# MEMS_RF.net
KiCad netlist of a schematic drawn in Altium Designer
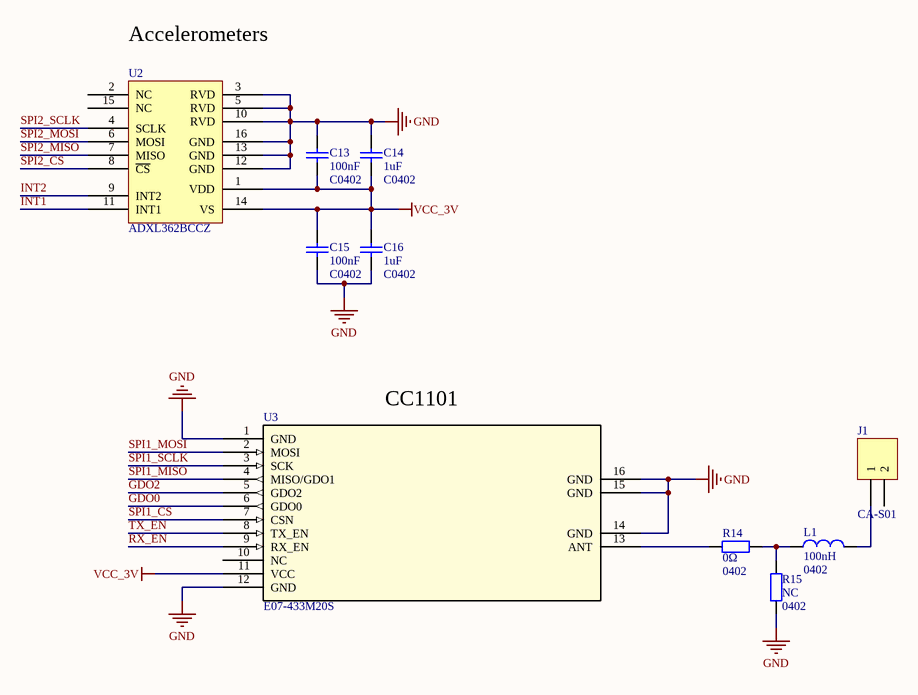
[diagram p0: MEMS&RF.SchDoc]

(export (version "E")
  (design (tool "Eeschema 10.0.6"))
  (components
    (comp (ref "C13")
      (value "100nF")
      (footprint "0402")
      (description "Capacitor (0402,X7R,100nF,DC 50V,±10%) Murata")
      (fields (field (name "PACKAGEREFERENCE") "C0402") (field (name "PUBLISHER") "Altium Limited"))
      (libsource (lib "RFID_CC1101_433MHz") (part "GRM155R71H104KE14"))
    )
    (comp (ref "C14")
      (value "1uF")
      (footprint "0402")
      (description "Capacitor (0402,X5R,1uF,DC 25V,±10%) Murata")
      (fields (field (name "PACKAGEREFERENCE") "C0402") (field (name "PUBLISHER") "Altium Limited"))
      (libsource (lib "RFID_CC1101_433MHz") (part "GRM155R61E105KE11"))
    )
    (comp (ref "C15")
      (value "100nF")
      (footprint "0402")
      (description "Capacitor (0402,X7R,100nF,DC 50V,±10%) Murata")
      (fields (field (name "PACKAGEREFERENCE") "C0402") (field (name "PUBLISHER") "Altium Limited"))
      (libsource (lib "RFID_CC1101_433MHz") (part "GRM155R71H104KE14"))
    )
    (comp (ref "C16")
      (value "1uF")
      (footprint "0402")
      (description "Capacitor (0402,X5R,1uF,DC 25V,±10%) Murata")
      (fields (field (name "PACKAGEREFERENCE") "C0402") (field (name "PUBLISHER") "Altium Limited"))
      (libsource (lib "RFID_CC1101_433MHz") (part "GRM155R61E105KE11"))
    )
    (comp (ref "J1")
      (value "CA-S01")
      (footprint "CA-S01")
      (description "CrossAir Antenna，广州寒武纪电子科技有限公司")
      (fields (field (name "PUBLISHER") "Altium Limited"))
      (libsource (lib "RFID_CC1101_433MHz") (part "CA-S01"))
    )
    (comp (ref "L1")
      (value "100nH")
      (footprint "0402")
      (description "Inductor, 100n, 0402, ±5%, wire-wound type Murata")
      (fields (field (name "PACKAGEREFERENCE") "0402") (field (name "PUBLISHER") "Altium Limited"))
      (libsource (lib "RFID_CC1101_433MHz") (part "LQW15ANR10J00"))
    )
    (comp (ref "R14")
      (value "0Ω")
      (footprint "RESC1005X04N")
      (description "Resistor 0402(1005) 0Ω")
      (fields (field (name "PACKAGEREFERENCE") "0402"))
      (libsource (lib "RFID_CC1101_433MHz") (part "RC0402JR"))
    )
    (comp (ref "R15")
      (value "NC")
      (footprint "RESC1005X04N")
      (description "Resistor 0402(1005) 0Ω")
      (fields (field (name "PACKAGEREFERENCE") "0402"))
      (libsource (lib "") (part "RC0402JR_1"))
    )
    (comp (ref "U2")
      (value "ADXL362BCCZ")
      (footprint "LGA_CC-16-4")
      (description "ADXL362, LGA, CC-16-4.")
      (libsource (lib "GPS_NB") (part "ADXL362BCCZ"))
    )
    (comp (ref "U3")
      (value "E07-433M20S")
      (footprint "PE07-433M20S")
      (libsource (lib "RFID_CC1101_433MHz") (part "E07-433M20S"))
    )
  )
  (nets
    (net (code "1") (name "/GDO0") (class "Default")
      (node (ref "U3") (pin "6") (pinfunction "GDO0_6") (pintype "output"))
    )
    (net (code "2") (name "/GDO2") (class "Default")
      (node (ref "U3") (pin "5") (pinfunction "GDO2_5") (pintype "output"))
    )
    (net (code "3") (name "/INT1") (class "Default")
      (node (ref "U2") (pin "11") (pinfunction "INT1_11") (pintype "passive"))
    )
    (net (code "4") (name "/INT2") (class "Default")
      (node (ref "U2") (pin "9") (pinfunction "INT2_9") (pintype "passive"))
    )
    (net (code "5") (name "/RX_EN") (class "Default")
      (node (ref "U3") (pin "9") (pinfunction "RX_EN_9") (pintype "input"))
    )
    (net (code "6") (name "/SPI1_CS") (class "Default")
      (node (ref "U3") (pin "7") (pinfunction "CSN_7") (pintype "input"))
    )
    (net (code "7") (name "/SPI1_MISO") (class "Default")
      (node (ref "U3") (pin "4") (pinfunction "MISO/GDO1_4") (pintype "output"))
    )
    (net (code "8") (name "/SPI1_MOSI") (class "Default")
      (node (ref "U3") (pin "2") (pinfunction "MOSI_2") (pintype "input"))
    )
    (net (code "9") (name "/SPI1_SCLK") (class "Default")
      (node (ref "U3") (pin "3") (pinfunction "SCK_3") (pintype "input"))
    )
    (net (code "10") (name "/SPI2_CS") (class "Default")
      (node (ref "U2") (pin "8") (pinfunction "~{CS}_8") (pintype "passive"))
    )
    (net (code "11") (name "/SPI2_MISO") (class "Default")
      (node (ref "U2") (pin "7") (pinfunction "MISO_7") (pintype "passive"))
    )
    (net (code "12") (name "/SPI2_MOSI") (class "Default")
      (node (ref "U2") (pin "6") (pinfunction "MOSI_6") (pintype "passive"))
    )
    (net (code "13") (name "/SPI2_SCLK") (class "Default")
      (node (ref "U2") (pin "4") (pinfunction "SCLK_4") (pintype "passive"))
    )
    (net (code "14") (name "/TX_EN") (class "Default")
      (node (ref "U3") (pin "8") (pinfunction "TX_EN_8") (pintype "input"))
    )
    (net (code "15") (name "GND") (class "Default")
      (node (ref "C13") (pin "2") (pinfunction "2_2") (pintype "passive"))
      (node (ref "C14") (pin "2") (pinfunction "2_2") (pintype "passive"))
      (node (ref "C15") (pin "2") (pinfunction "2_2") (pintype "passive"))
      (node (ref "C16") (pin "1") (pinfunction "1_1") (pintype "passive"))
      (node (ref "R15") (pin "1") (pinfunction "1_1") (pintype "passive"))
      (node (ref "U2") (pin "10") (pinfunction "RVD_10") (pintype "passive"))
      (node (ref "U2") (pin "12") (pinfunction "GND_12") (pintype "passive"))
      (node (ref "U2") (pin "13") (pinfunction "GND_13") (pintype "passive"))
      (node (ref "U2") (pin "16") (pinfunction "GND_16") (pintype "passive"))
      (node (ref "U2") (pin "3") (pinfunction "RVD_3") (pintype "passive"))
      (node (ref "U2") (pin "5") (pinfunction "RVD_5") (pintype "passive"))
      (node (ref "U3") (pin "1") (pinfunction "GND_1") (pintype "power_in"))
      (node (ref "U3") (pin "12") (pinfunction "GND_12") (pintype "power_in"))
      (node (ref "U3") (pin "14") (pinfunction "GND_14") (pintype "power_in"))
      (node (ref "U3") (pin "15") (pinfunction "GND_15") (pintype "power_in"))
      (node (ref "U3") (pin "16") (pinfunction "GND_16") (pintype "power_in"))
    )
    (net (code "16") (name "Net-(J1-Pad1)") (class "Default")
      (node (ref "J1") (pin "1") (pinfunction "1_1") (pintype "passive"))
      (node (ref "L1") (pin "2") (pinfunction "2_2") (pintype "passive"))
    )
    (net (code "17") (name "Net-(L1-Pad1)") (class "Default")
      (node (ref "L1") (pin "1") (pinfunction "1_1") (pintype "passive"))
      (node (ref "R14") (pin "2") (pinfunction "2_2") (pintype "passive"))
      (node (ref "R15") (pin "2") (pinfunction "2_2") (pintype "passive"))
    )
    (net (code "18") (name "Net-(U3-ANT)") (class "Default")
      (node (ref "R14") (pin "1") (pinfunction "1_1") (pintype "passive"))
      (node (ref "U3") (pin "13") (pinfunction "ANT_13") (pintype "passive"))
    )
    (net (code "19") (name "VCC_3V") (class "Default")
      (node (ref "C13") (pin "1") (pinfunction "1_1") (pintype "passive"))
      (node (ref "C14") (pin "1") (pinfunction "1_1") (pintype "passive"))
      (node (ref "C15") (pin "1") (pinfunction "1_1") (pintype "passive"))
      (node (ref "C16") (pin "2") (pinfunction "2_2") (pintype "passive"))
      (node (ref "U2") (pin "1") (pinfunction "VDD_1") (pintype "passive"))
      (node (ref "U2") (pin "14") (pinfunction "VS_14") (pintype "passive"))
      (node (ref "U3") (pin "11") (pinfunction "VCC_11") (pintype "power_in"))
    )
    (net (code "20") (name "unconnected-(J1-Pad2)") (class "Default")
      (node (ref "J1") (pin "2") (pinfunction "2_2") (pintype "passive"))
    )
    (net (code "21") (name "unconnected-(U2-NC-Pad2)") (class "Default")
      (node (ref "U2") (pin "2") (pinfunction "NC_2") (pintype "passive"))
    )
    (net (code "22") (name "unconnected-(U2-NC-Pad15)") (class "Default")
      (node (ref "U2") (pin "15") (pinfunction "NC_15") (pintype "passive"))
    )
    (net (code "23") (name "unconnected-(U3-NC-Pad10)") (class "Default")
      (node (ref "U3") (pin "10") (pinfunction "NC_10") (pintype "passive"))
    )
  )
)
